# revA.net
KiCad netlist of a schematic drawn in EAGLE
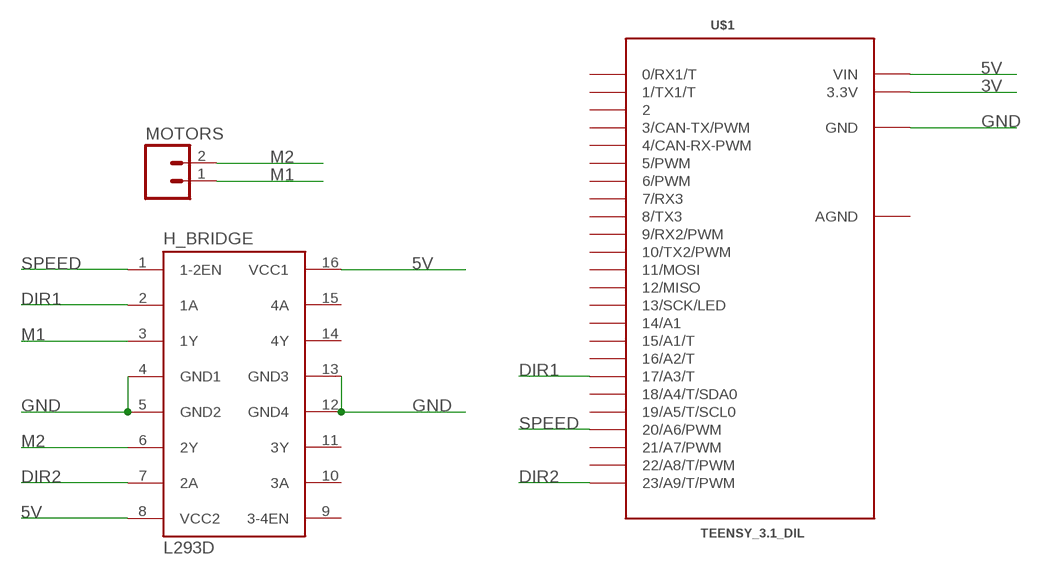
[diagram p0: schematic, sheet 1]

(export (version "E")
  (design (tool "Eeschema 10.0.6"))
  (components
    (comp (ref "H_BRIDGE")
      (value "L293D")
      (footprint "eagle-import:DIL16")
      (libsource (lib "eagle-import") (part "L293D"))
    )
    (comp (ref "MOTORS")
      (value "M02JST-PTH-2")
      (footprint "eagle-import:JST-2-PTH")
      (libsource (lib "eagle-import") (part "M02JST-PTH-2"))
    )
    (comp (ref "U$1")
      (value "TEENSY_3.1_DIL")
      (footprint "eagle-import:TEENSY3-DIL")
      (libsource (lib "eagle-import") (part "TEENSY_3.1_DIL"))
    )
  )
  (nets
    (net (code "1") (name "/3V") (class "Default")
      (node (ref "U$1") (pin "3.3V") (pinfunction "3.3V_3.3V") (pintype "power_in"))
    )
    (net (code "2") (name "/5V") (class "Default")
      (node (ref "H_BRIDGE") (pin "16") (pinfunction "VCC1_16") (pintype "power_in"))
      (node (ref "H_BRIDGE") (pin "8") (pinfunction "VCC2_8") (pintype "power_in"))
      (node (ref "U$1") (pin "VIN") (pinfunction "VIN_VIN") (pintype "power_in"))
    )
    (net (code "3") (name "/AGND") (class "Default")
      (node (ref "U$1") (pin "AGND") (pinfunction "AGND_AGND") (pintype "power_in"))
    )
    (net (code "4") (name "/DIR1") (class "Default")
      (node (ref "H_BRIDGE") (pin "2") (pinfunction "1A_2") (pintype "input"))
      (node (ref "U$1") (pin "17/A3") (pinfunction "17/A3/T_17/A3") (pintype "bidirectional"))
    )
    (net (code "5") (name "/DIR2") (class "Default")
      (node (ref "H_BRIDGE") (pin "7") (pinfunction "2A_7") (pintype "input"))
      (node (ref "U$1") (pin "23/A9") (pinfunction "23/A9/T/PWM_23/A9") (pintype "bidirectional"))
    )
    (net (code "6") (name "/GND") (class "Default")
      (node (ref "H_BRIDGE") (pin "12") (pinfunction "GND4_12") (pintype "power_in"))
      (node (ref "H_BRIDGE") (pin "13") (pinfunction "GND3_13") (pintype "power_in"))
      (node (ref "H_BRIDGE") (pin "4") (pinfunction "GND1_4") (pintype "power_in"))
      (node (ref "H_BRIDGE") (pin "5") (pinfunction "GND2_5") (pintype "power_in"))
      (node (ref "U$1") (pin "GND") (pinfunction "GND_GND") (pintype "power_in"))
    )
    (net (code "7") (name "/M1") (class "Default")
      (node (ref "H_BRIDGE") (pin "3") (pinfunction "1Y_3") (pintype "output"))
      (node (ref "MOTORS") (pin "1") (pinfunction "1_1") (pintype "passive"))
    )
    (net (code "8") (name "/M2") (class "Default")
      (node (ref "H_BRIDGE") (pin "6") (pinfunction "2Y_6") (pintype "output"))
      (node (ref "MOTORS") (pin "2") (pinfunction "2_2") (pintype "passive"))
    )
    (net (code "9") (name "/SPEED") (class "Default")
      (node (ref "H_BRIDGE") (pin "1") (pinfunction "1-2EN_1") (pintype "input"))
      (node (ref "U$1") (pin "20/A6") (pinfunction "20/A6/PWM_20/A6") (pintype "bidirectional"))
    )
    (net (code "10") (name "unconnected-(H_BRIDGE-3-4EN-Pad9)") (class "Default")
      (node (ref "H_BRIDGE") (pin "9") (pinfunction "3-4EN_9") (pintype "input"))
    )
    (net (code "11") (name "unconnected-(H_BRIDGE-3A-Pad10)") (class "Default")
      (node (ref "H_BRIDGE") (pin "10") (pinfunction "3A_10") (pintype "input"))
    )
    (net (code "12") (name "unconnected-(H_BRIDGE-3Y-Pad11)") (class "Default")
      (node (ref "H_BRIDGE") (pin "11") (pinfunction "3Y_11") (pintype "output"))
    )
    (net (code "13") (name "unconnected-(H_BRIDGE-4A-Pad15)") (class "Default")
      (node (ref "H_BRIDGE") (pin "15") (pinfunction "4A_15") (pintype "input"))
    )
    (net (code "14") (name "unconnected-(H_BRIDGE-4Y-Pad14)") (class "Default")
      (node (ref "H_BRIDGE") (pin "14") (pinfunction "4Y_14") (pintype "output"))
    )
    (net (code "15") (name "unconnected-(U$1-0{slash}RX1{slash}T-Pad0)") (class "Default")
      (node (ref "U$1") (pin "0") (pinfunction "0/RX1/T_0") (pintype "bidirectional"))
    )
    (net (code "16") (name "unconnected-(U$1-1{slash}TX1{slash}T-Pad1)") (class "Default")
      (node (ref "U$1") (pin "1") (pinfunction "1/TX1/T_1") (pintype "bidirectional"))
    )
    (net (code "17") (name "unconnected-(U$1-3{slash}CAN-TX{slash}PWM-Pad3)") (class "Default")
      (node (ref "U$1") (pin "3") (pinfunction "3/CAN-TX/PWM_3") (pintype "bidirectional"))
    )
    (net (code "18") (name "unconnected-(U$1-4{slash}CAN-RX-PWM-Pad4)") (class "Default")
      (node (ref "U$1") (pin "4") (pinfunction "4/CAN-RX-PWM_4") (pintype "bidirectional"))
    )
    (net (code "19") (name "unconnected-(U$1-5{slash}PWM-Pad5)") (class "Default")
      (node (ref "U$1") (pin "5") (pinfunction "5/PWM_5") (pintype "bidirectional"))
    )
    (net (code "20") (name "unconnected-(U$1-6{slash}PWM-Pad6)") (class "Default")
      (node (ref "U$1") (pin "6") (pinfunction "6/PWM_6") (pintype "bidirectional"))
    )
    (net (code "21") (name "unconnected-(U$1-7{slash}RX3-Pad7)") (class "Default")
      (node (ref "U$1") (pin "7") (pinfunction "7/RX3_7") (pintype "bidirectional"))
    )
    (net (code "22") (name "unconnected-(U$1-8{slash}TX3-Pad8)") (class "Default")
      (node (ref "U$1") (pin "8") (pinfunction "8/TX3_8") (pintype "bidirectional"))
    )
    (net (code "23") (name "unconnected-(U$1-9{slash}RX2{slash}PWM-Pad9)") (class "Default")
      (node (ref "U$1") (pin "9") (pinfunction "9/RX2/PWM_9") (pintype "bidirectional"))
    )
    (net (code "24") (name "unconnected-(U$1-10{slash}TX2{slash}PWM-Pad10)") (class "Default")
      (node (ref "U$1") (pin "10") (pinfunction "10/TX2/PWM_10") (pintype "bidirectional"))
    )
    (net (code "25") (name "unconnected-(U$1-11{slash}MOSI-Pad11)") (class "Default")
      (node (ref "U$1") (pin "11") (pinfunction "11/MOSI_11") (pintype "bidirectional"))
    )
    (net (code "26") (name "unconnected-(U$1-12{slash}MISO-Pad12)") (class "Default")
      (node (ref "U$1") (pin "12") (pinfunction "12/MISO_12") (pintype "bidirectional"))
    )
    (net (code "27") (name "unconnected-(U$1-13{slash}SCK{slash}LED-Pad13)") (class "Default")
      (node (ref "U$1") (pin "13") (pinfunction "13/SCK/LED_13") (pintype "bidirectional"))
    )
    (net (code "28") (name "unconnected-(U$1-14{slash}A1-Pad14{slash}A0)") (class "Default")
      (node (ref "U$1") (pin "14/A0") (pinfunction "14/A1_14/A0") (pintype "bidirectional"))
    )
    (net (code "29") (name "unconnected-(U$1-15{slash}A1{slash}T-Pad15{slash}A1)") (class "Default")
      (node (ref "U$1") (pin "15/A1") (pinfunction "15/A1/T_15/A1") (pintype "bidirectional"))
    )
    (net (code "30") (name "unconnected-(U$1-16{slash}A2{slash}T-Pad16{slash}A2)") (class "Default")
      (node (ref "U$1") (pin "16/A2") (pinfunction "16/A2/T_16/A2") (pintype "bidirectional"))
    )
    (net (code "31") (name "unconnected-(U$1-18{slash}A4{slash}T{slash}SDA0-Pad18{slash}A4)") (class "Default")
      (node (ref "U$1") (pin "18/A4") (pinfunction "18/A4/T/SDA0_18/A4") (pintype "bidirectional"))
    )
    (net (code "32") (name "unconnected-(U$1-19{slash}A5{slash}T{slash}SCL0-Pad19{slash}A5)") (class "Default")
      (node (ref "U$1") (pin "19/A5") (pinfunction "19/A5/T/SCL0_19/A5") (pintype "bidirectional"))
    )
    (net (code "33") (name "unconnected-(U$1-21{slash}A7{slash}PWM-Pad21{slash}A7)") (class "Default")
      (node (ref "U$1") (pin "21/A7") (pinfunction "21/A7/PWM_21/A7") (pintype "bidirectional"))
    )
    (net (code "34") (name "unconnected-(U$1-22{slash}A8{slash}T{slash}PWM-Pad22{slash}A8)") (class "Default")
      (node (ref "U$1") (pin "22/A8") (pinfunction "22/A8/T/PWM_22/A8") (pintype "bidirectional"))
    )
    (net (code "35") (name "unconnected-(U$1-Pad2)") (class "Default")
      (node (ref "U$1") (pin "2") (pinfunction "2_2") (pintype "bidirectional"))
    )
  )
)
